# SCH_n2_power_distribution_board_2022-03-.net
KiCad netlist of a schematic drawn in EasyEDA
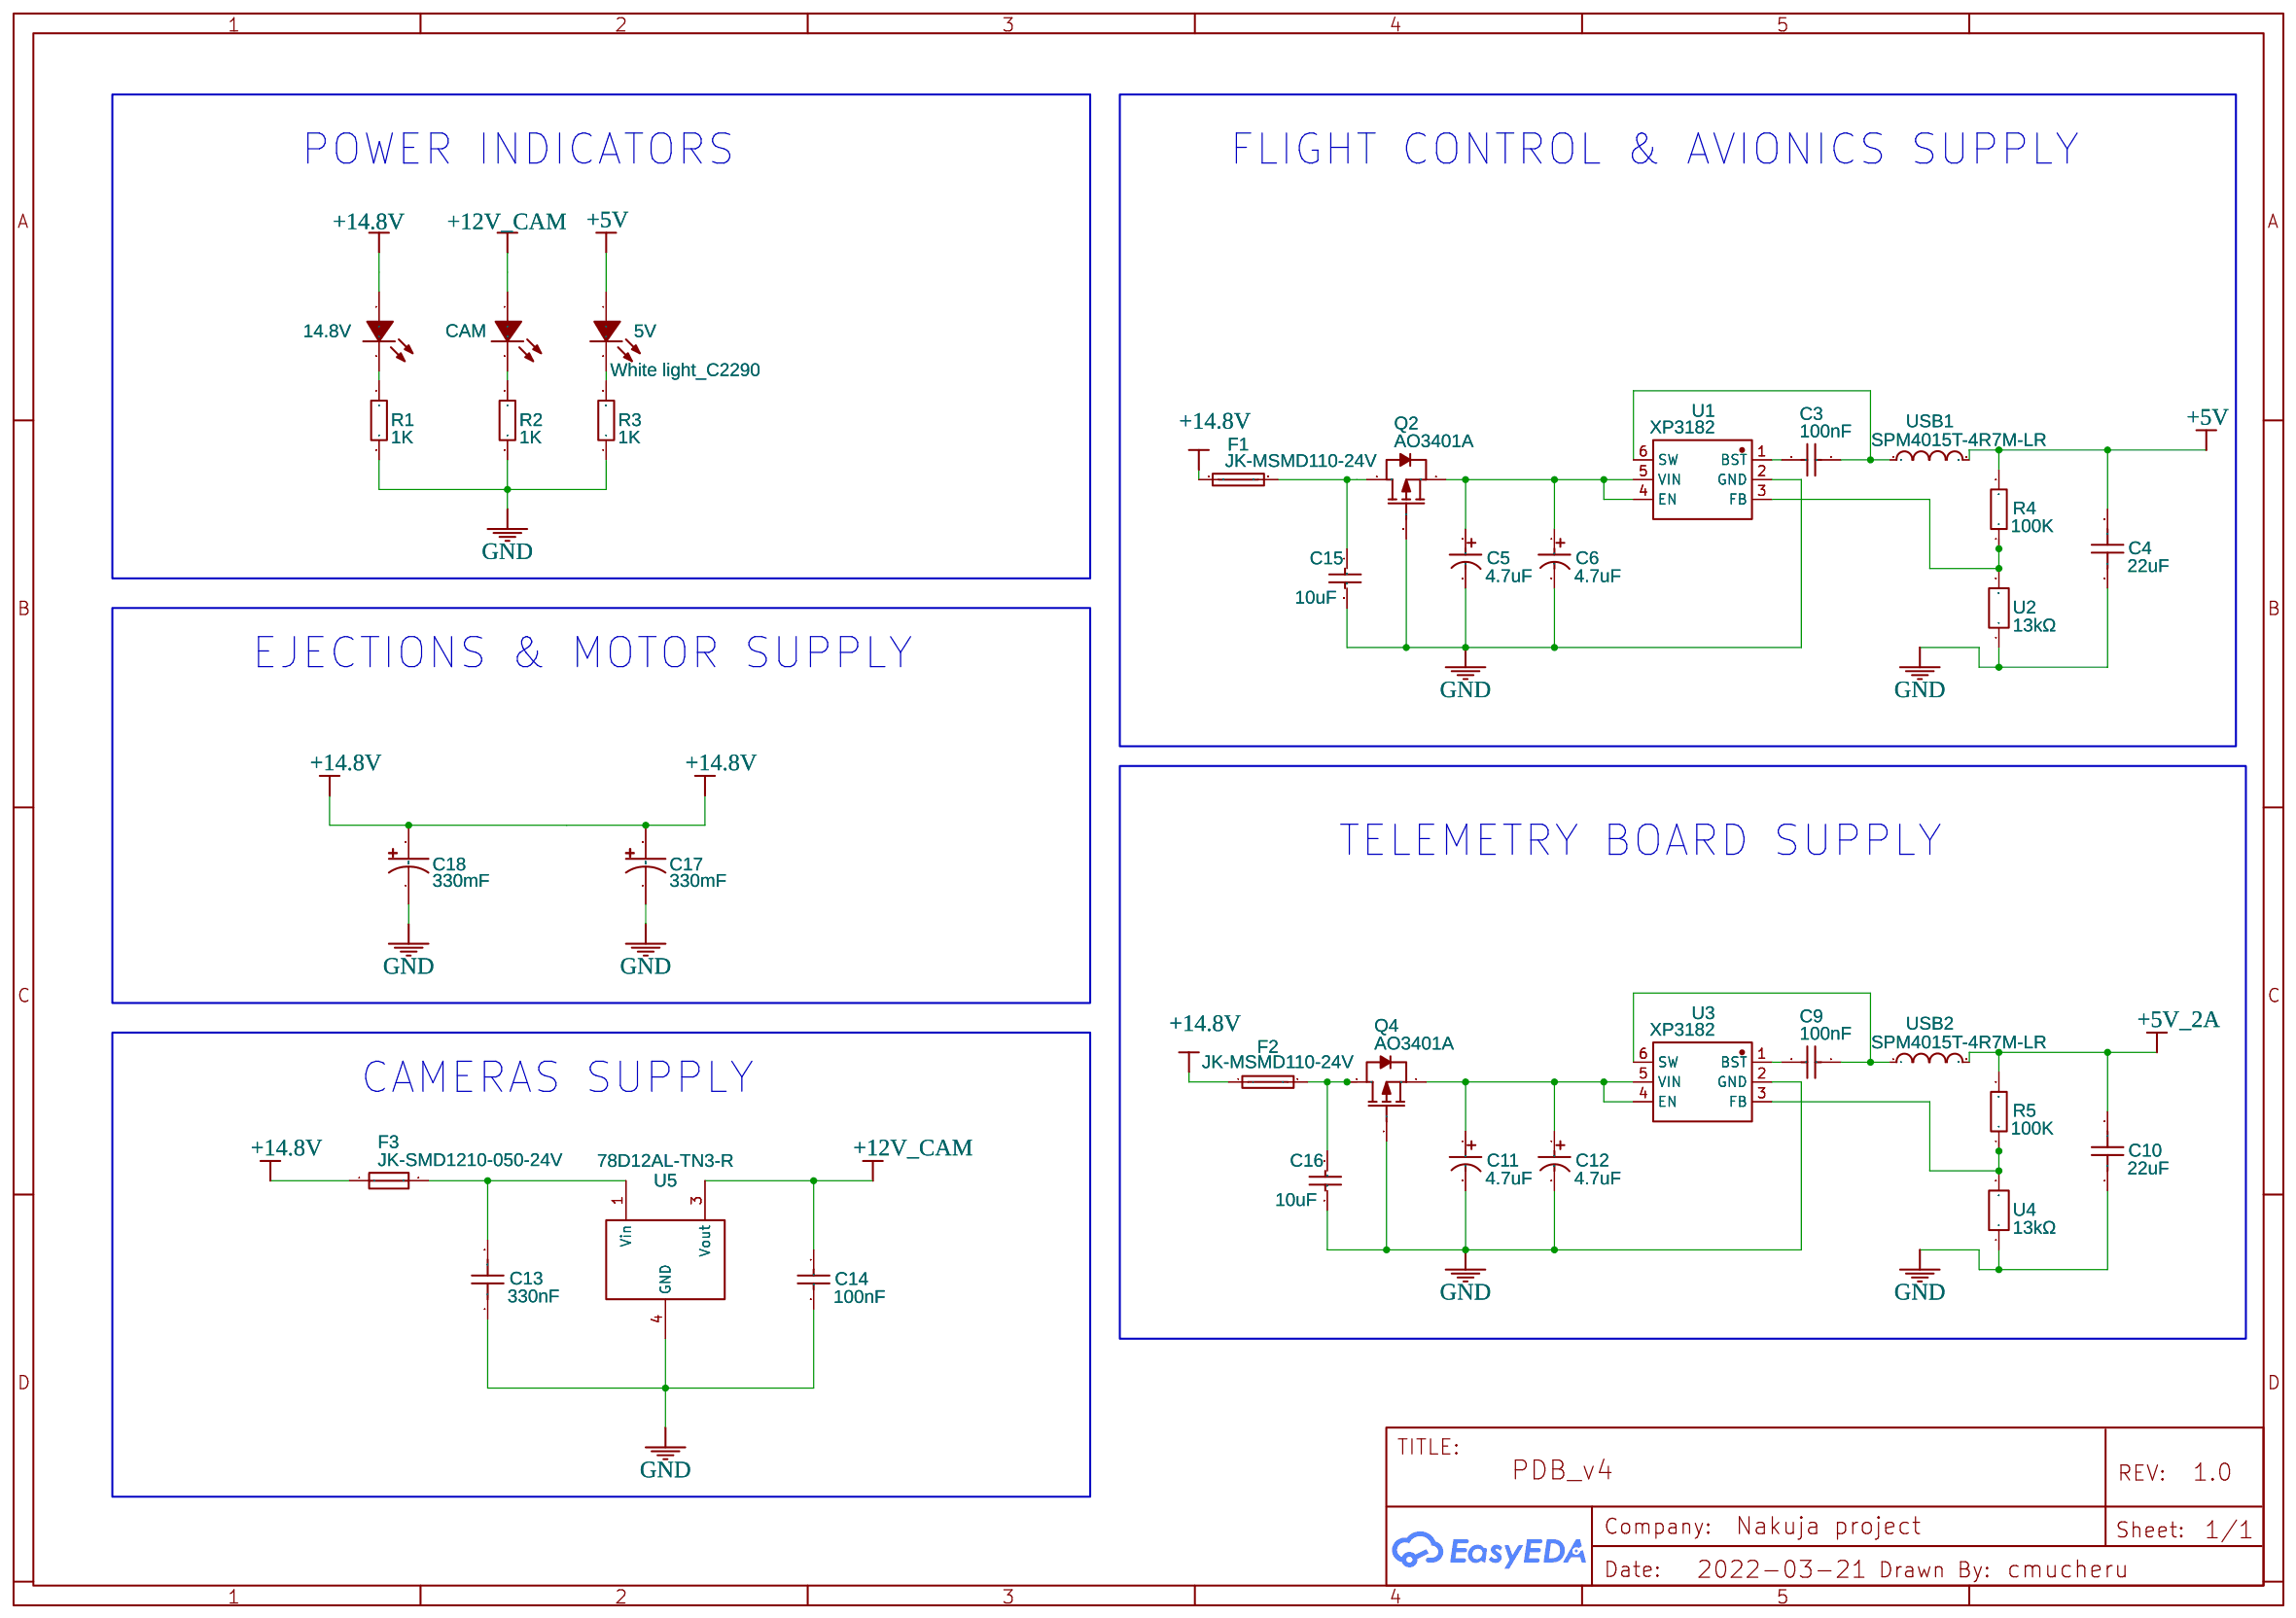
[diagram p0: PDB]
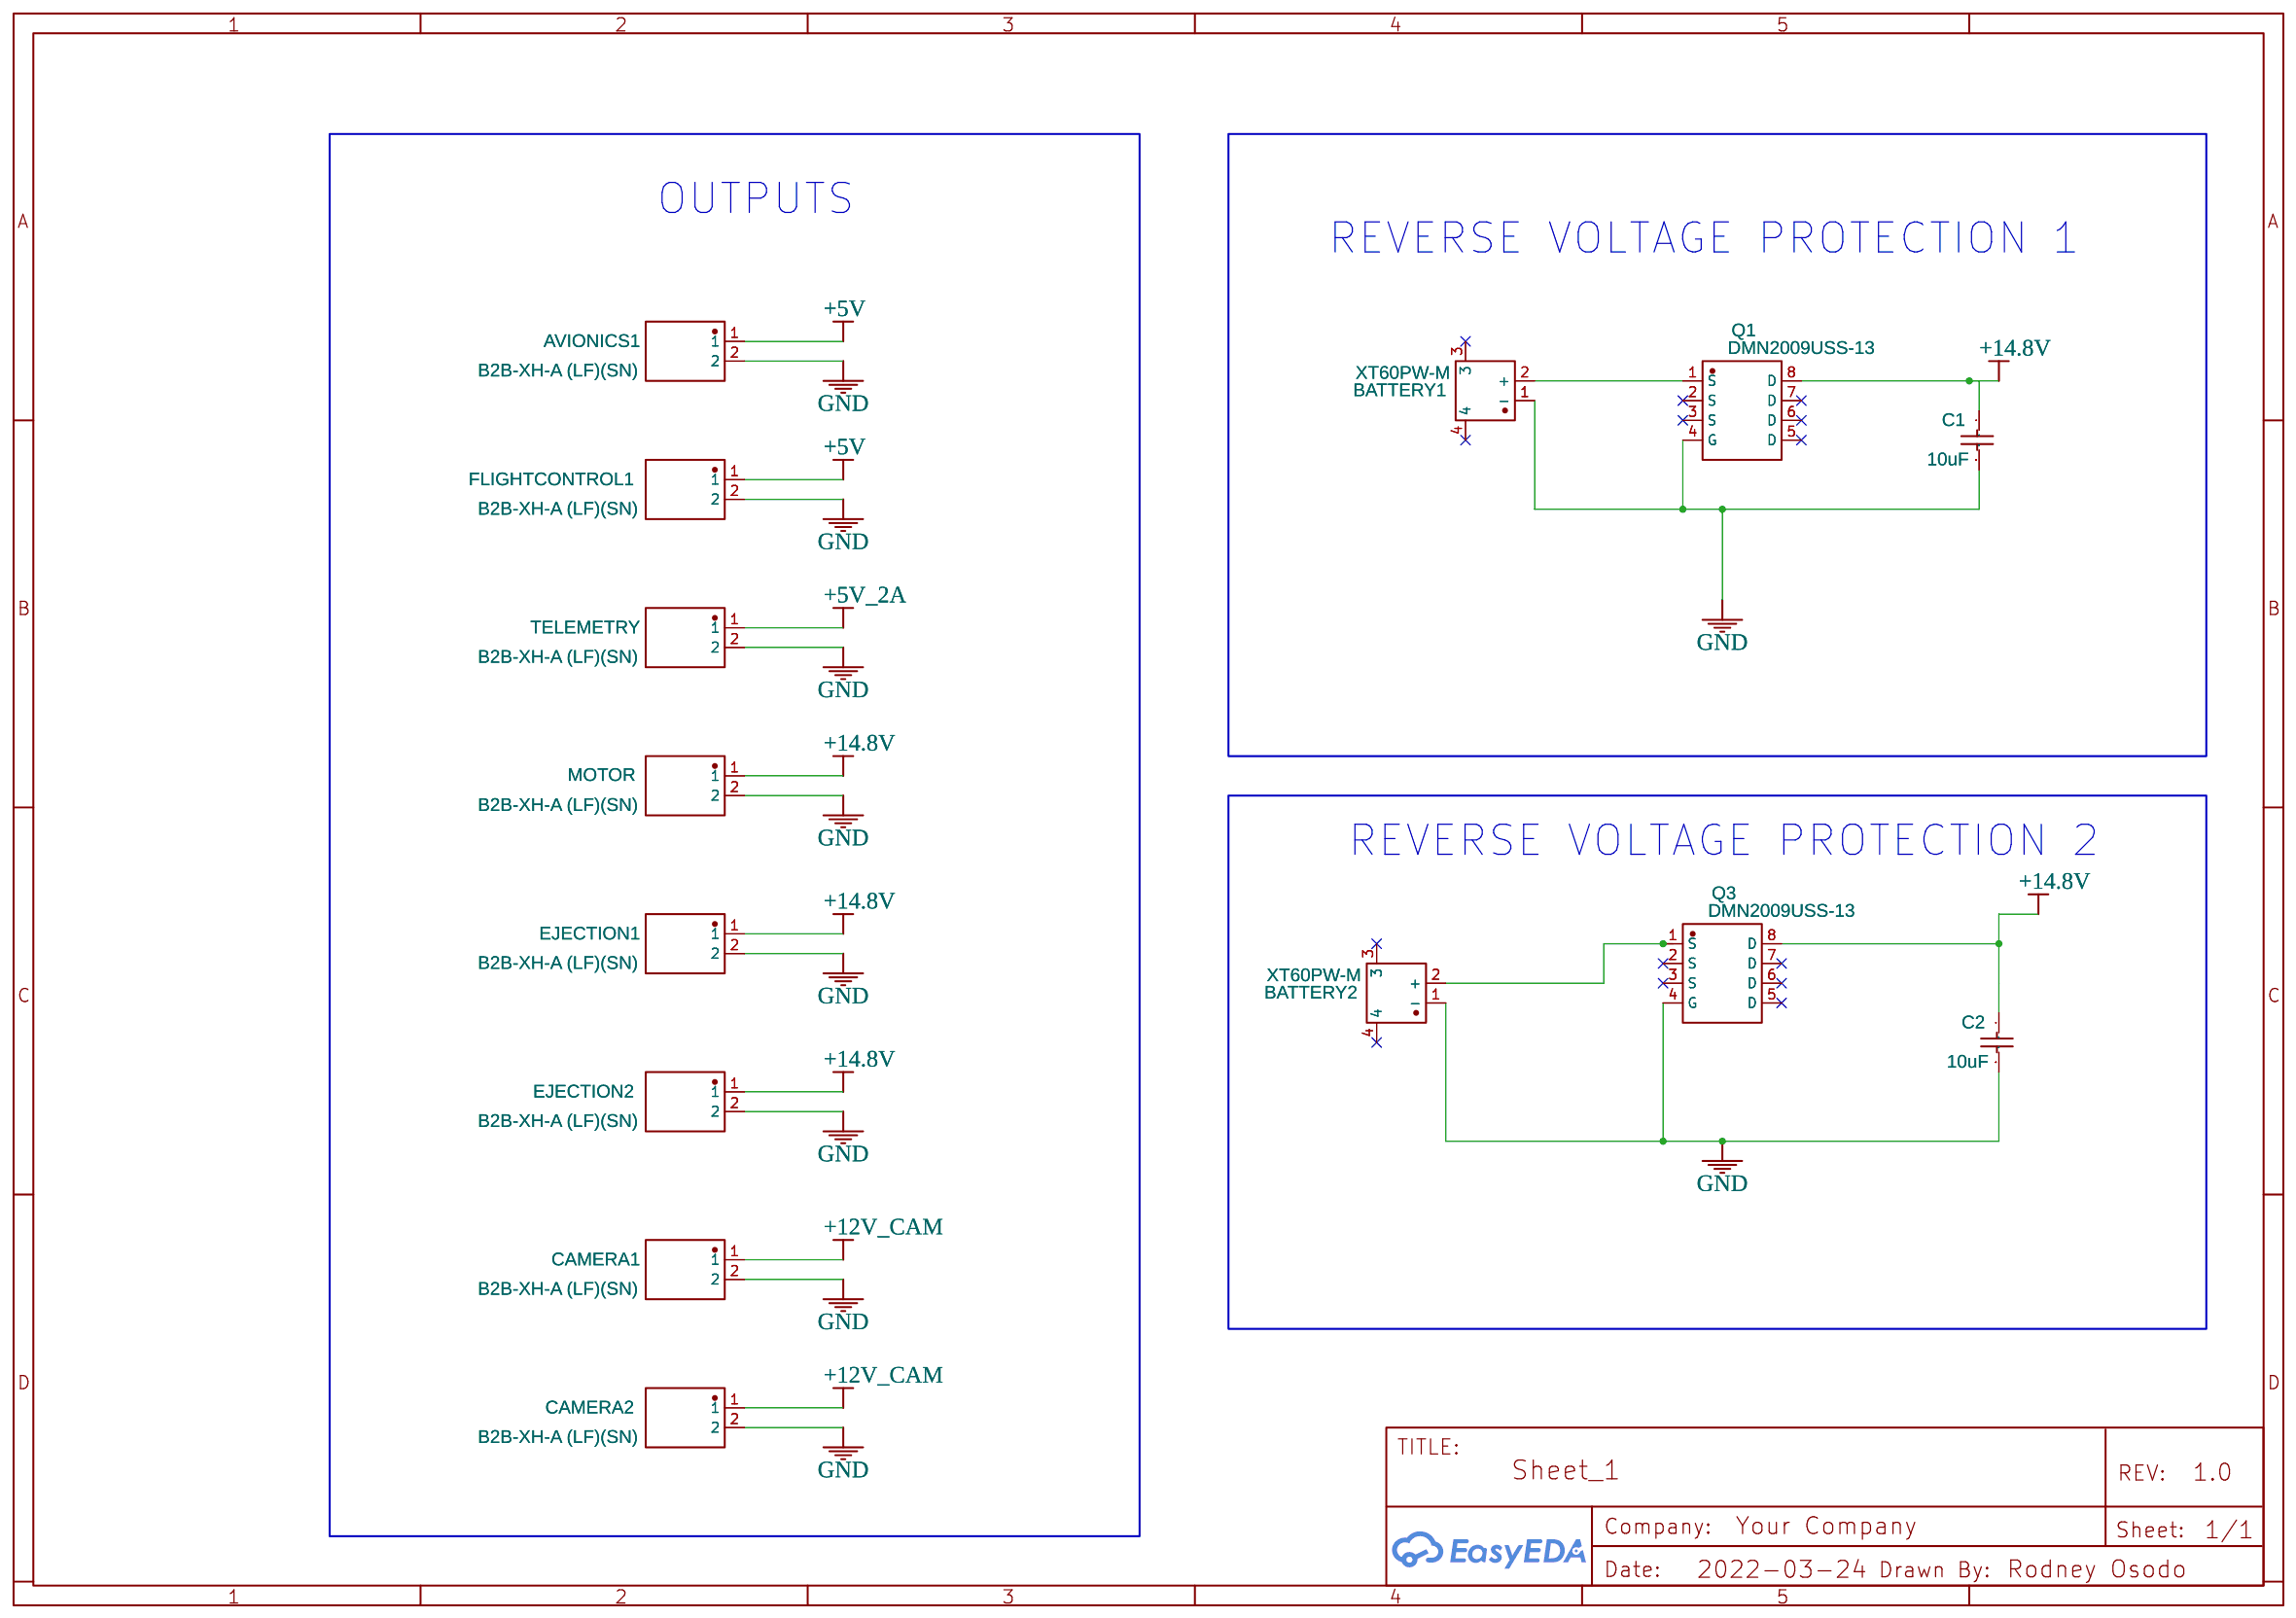
[diagram p1: Connectors]

(export (version "E")
  (design (tool "Eeschema 10.0.6"))
  (components
    (comp (ref "5V")
      (value "White light_C2290")
      (fields
        (field (name "BOM_Manufacturer Part") "0603White light")
        (field (name "BOM_Supplier Part") "C2290")
      )
      (libsource (lib "") (part "0603White light_C2290"))
    )
    (comp (ref "14.8V")
      (value "White light_C2290")
      (fields
        (field (name "BOM_Manufacturer Part") "0603White light")
        (field (name "BOM_Supplier Part") "C2290")
      )
      (libsource (lib "") (part "0603White light_C2290_2"))
    )
    (comp (ref "C3")
      (value "100nF")
      (fields
        (field (name "BOM_Manufacturer Part") "CL05B104KO5NNNC")
        (field (name "BOM_Supplier Part") "C1525")
      )
      (libsource (lib "") (part "CL05B104KO5NNNC_1"))
    )
    (comp (ref "C4")
      (value "22uF")
      (fields
        (field (name "BOM_Manufacturer Part") "GRM155R60J226ME11D")
        (field (name "BOM_Supplier Part") "C415703")
      )
      (libsource (lib "") (part "GRM155R60J226ME11D"))
    )
    (comp (ref "C5")
      (value "4.7uF")
      (fields
        (field (name "BOM_Manufacturer Part") "RVT1V4R7M0405")
        (field (name "BOM_Supplier Part") "C72511")
      )
      (libsource (lib "") (part "RVT1V4R7M0405"))
    )
    (comp (ref "C6")
      (value "4.7uF")
      (fields
        (field (name "BOM_Manufacturer Part") "RVT1V4R7M0405")
        (field (name "BOM_Supplier Part") "C72511")
      )
      (libsource (lib "") (part "RVT1V4R7M0405"))
    )
    (comp (ref "C9")
      (value "100nF")
      (fields
        (field (name "BOM_Manufacturer Part") "CL05B104KO5NNNC")
        (field (name "BOM_Supplier Part") "C1525")
      )
      (libsource (lib "") (part "CL05B104KO5NNNC_1"))
    )
    (comp (ref "C10")
      (value "22uF")
      (fields
        (field (name "BOM_Manufacturer Part") "GRM155R60J226ME11D")
        (field (name "BOM_Supplier Part") "C415703")
      )
      (libsource (lib "") (part "GRM155R60J226ME11D"))
    )
    (comp (ref "C11")
      (value "4.7uF")
      (fields
        (field (name "BOM_Manufacturer Part") "RVT1V4R7M0405")
        (field (name "BOM_Supplier Part") "C72511")
      )
      (libsource (lib "") (part "RVT1V4R7M0405"))
    )
    (comp (ref "C12")
      (value "4.7uF")
      (fields
        (field (name "BOM_Manufacturer Part") "RVT1V4R7M0405")
        (field (name "BOM_Supplier Part") "C72511")
      )
      (libsource (lib "") (part "RVT1V4R7M0405"))
    )
    (comp (ref "C13")
      (value "330nF")
      (fields
        (field (name "BOM_Manufacturer Part") "CC0402ZRY5V7BB334")
        (field (name "BOM_Supplier Part") "C527033")
      )
      (libsource (lib "") (part "CC0402ZRY5V7BB334"))
    )
    (comp (ref "C14")
      (value "100nF")
      (fields
        (field (name "BOM_Manufacturer Part") "CL05B104KO5NNNC")
        (field (name "BOM_Supplier Part") "C1525")
      )
      (libsource (lib "") (part "CL05B104KO5NNNC"))
    )
    (comp (ref "C15")
      (value "10uF")
      (fields
        (field (name "BOM_Manufacturer Part") "CL05A106MQ5NUNC")
        (field (name "BOM_Supplier Part") "C15525")
      )
      (libsource (lib "") (part "CL05A106MQ5NUNC"))
    )
    (comp (ref "C16")
      (value "10uF")
      (fields
        (field (name "BOM_Manufacturer Part") "CL05A106MQ5NUNC")
        (field (name "BOM_Supplier Part") "C15525")
      )
      (libsource (lib "") (part "CL05A106MQ5NUNC"))
    )
    (comp (ref "C17")
      (value "330mF")
      (fields
        (field (name "BOM_Manufacturer Part") "EECS0HD334H")
        (field (name "BOM_Supplier Part") "C128528")
      )
      (libsource (lib "") (part "EECS0HD334H_1"))
    )
    (comp (ref "C18")
      (value "330mF")
      (fields
        (field (name "BOM_Manufacturer Part") "EECS0HD334H")
        (field (name "BOM_Supplier Part") "C128528")
      )
      (libsource (lib "") (part "EECS0HD334H"))
    )
    (comp (ref "CAM")
      (value "White light_C2290")
      (fields
        (field (name "BOM_Manufacturer Part") "0603White light")
        (field (name "BOM_Supplier Part") "C2290")
      )
      (libsource (lib "") (part "0603White light_C2290_1"))
    )
    (comp (ref "F1")
      (value "JK-MSMD110-24V")
      (fields (field (name "BOM_Supplier Part") "C369172"))
      (libsource (lib "") (part "JK-MSMD110-24V"))
    )
    (comp (ref "F2")
      (value "JK-MSMD110-24V")
      (fields (field (name "BOM_Supplier Part") "C369172"))
      (libsource (lib "") (part "JK-MSMD110-24V"))
    )
    (comp (ref "F3")
      (value "JK-SMD1210-050-24V")
      (fields (field (name "BOM_Supplier Part") "C720078"))
      (libsource (lib "") (part "JK-SMD1210-050-24V"))
    )
    (comp (ref "Q2")
      (value "AO3401A")
      (fields (field (name "BOM_Supplier Part") "C15127"))
      (libsource (lib "") (part "AO3401A"))
    )
    (comp (ref "Q4")
      (value "AO3401A")
      (fields (field (name "BOM_Supplier Part") "C15127"))
      (libsource (lib "") (part "AO3401A"))
    )
    (comp (ref "R1")
      (value "1K")
      (fields
        (field (name "BOM_Manufacturer Part") "0402WGF5101TCE")
        (field (name "BOM_Supplier Part") "C25905")
      )
      (libsource (lib "") (part "0402WGF5101TCE"))
    )
    (comp (ref "R2")
      (value "1K")
      (fields
        (field (name "BOM_Manufacturer Part") "0402WGF5101TCE")
        (field (name "BOM_Supplier Part") "C25905")
      )
      (libsource (lib "") (part "0402WGF5101TCE"))
    )
    (comp (ref "R3")
      (value "1K")
      (fields
        (field (name "BOM_Manufacturer Part") "0402WGF5101TCE")
        (field (name "BOM_Supplier Part") "C25905")
      )
      (libsource (lib "") (part "0402WGF5101TCE_1"))
    )
    (comp (ref "R4")
      (value "100K")
      (fields
        (field (name "BOM_Manufacturer Part") "0402WGF1003TCE")
        (field (name "BOM_Supplier Part") "C25741")
      )
      (libsource (lib "") (part "0402WGF1003TCE"))
    )
    (comp (ref "R5")
      (value "100K")
      (fields
        (field (name "BOM_Manufacturer Part") "0402WGF1003TCE")
        (field (name "BOM_Supplier Part") "C25741")
      )
      (libsource (lib "") (part "0402WGF1003TCE"))
    )
    (comp (ref "U1")
      (value "XP3182")
      (fields (field (name "BOM_Supplier Part") "C2802261"))
      (libsource (lib "") (part "XP3182"))
    )
    (comp (ref "U2")
      (value "13kΩ")
      (fields
        (field (name "BOM_Manufacturer Part") "PTFR0402B13K0P9")
        (field (name "BOM_Supplier Part") "C2693072")
      )
      (libsource (lib "") (part "PTFR0402B13K0P9"))
    )
    (comp (ref "U3")
      (value "XP3182")
      (fields (field (name "BOM_Supplier Part") "C2802261"))
      (libsource (lib "") (part "XP3182"))
    )
    (comp (ref "U4")
      (value "13kΩ")
      (fields
        (field (name "BOM_Manufacturer Part") "PTFR0402B13K0P9")
        (field (name "BOM_Supplier Part") "C2693072")
      )
      (libsource (lib "") (part "PTFR0402B13K0P9"))
    )
    (comp (ref "U5")
      (value "78D12AL-TN3-R")
      (fields (field (name "BOM_Supplier Part") "C73290"))
      (libsource (lib "") (part "78D12AL-TN3-R"))
    )
    (comp (ref "USB1")
      (value "SPM4015T-4R7M-LR")
      (fields (field (name "BOM_Supplier Part") "C2052599"))
      (libsource (lib "") (part "SPM4015T-4R7M-LR"))
    )
    (comp (ref "USB2")
      (value "SPM4015T-4R7M-LR")
      (fields (field (name "BOM_Supplier Part") "C2052599"))
      (libsource (lib "") (part "SPM4015T-4R7M-LR"))
    )
    (comp (ref "AVIONICS1")
      (value "B2B-XH-A (LF)(SN)")
      (fields (field (name "BOM_Supplier Part") "C158012"))
      (libsource (lib "") (part "B2B-XH-A (LF)(SN)"))
    )
    (comp (ref "BATTERY1")
      (value "XT60PW-M")
      (fields (field (name "BOM_Supplier Part") "C98732"))
      (libsource (lib "") (part "XT60PW-M"))
    )
    (comp (ref "BATTERY2")
      (value "XT60PW-M")
      (fields (field (name "BOM_Supplier Part") "C98732"))
      (libsource (lib "") (part "XT60PW-M"))
    )
    (comp (ref "C1")
      (value "10uF")
      (fields
        (field (name "BOM_Manufacturer Part") "CL05A106MQ5NUNC")
        (field (name "BOM_Supplier Part") "C15525")
      )
      (libsource (lib "") (part "CL05A106MQ5NUNC"))
    )
    (comp (ref "C2")
      (value "10uF")
      (fields
        (field (name "BOM_Manufacturer Part") "CL05A106MQ5NUNC")
        (field (name "BOM_Supplier Part") "C15525")
      )
      (libsource (lib "") (part "CL05A106MQ5NUNC"))
    )
    (comp (ref "CAMERA1")
      (value "B2B-XH-A (LF)(SN)")
      (fields (field (name "BOM_Supplier Part") "C158012"))
      (libsource (lib "") (part "B2B-XH-A (LF)(SN)_2"))
    )
    (comp (ref "CAMERA2")
      (value "B2B-XH-A (LF)(SN)")
      (fields (field (name "BOM_Supplier Part") "C158012"))
      (libsource (lib "") (part "B2B-XH-A (LF)(SN)_2"))
    )
    (comp (ref "EJECTION1")
      (value "B2B-XH-A (LF)(SN)")
      (fields (field (name "BOM_Supplier Part") "C158012"))
      (libsource (lib "") (part "B2B-XH-A (LF)(SN)_1"))
    )
    (comp (ref "EJECTION2")
      (value "B2B-XH-A (LF)(SN)")
      (fields (field (name "BOM_Supplier Part") "C158012"))
      (libsource (lib "") (part "B2B-XH-A (LF)(SN)_1"))
    )
    (comp (ref "FLIGHTCONTROL1")
      (value "B2B-XH-A (LF)(SN)")
      (fields (field (name "BOM_Supplier Part") "C158012"))
      (libsource (lib "") (part "B2B-XH-A (LF)(SN)_4"))
    )
    (comp (ref "MOTOR")
      (value "B2B-XH-A (LF)(SN)")
      (fields (field (name "BOM_Supplier Part") "C158012"))
      (libsource (lib "") (part "B2B-XH-A (LF)(SN)_5"))
    )
    (comp (ref "Q1")
      (value "DMN2009USS-13")
      (fields (field (name "BOM_Supplier Part") "C460995"))
      (libsource (lib "") (part "DMN2009USS-13"))
    )
    (comp (ref "Q3")
      (value "DMN2009USS-13")
      (fields (field (name "BOM_Supplier Part") "C460995"))
      (libsource (lib "") (part "DMN2009USS-13"))
    )
    (comp (ref "TELEMETRY")
      (value "B2B-XH-A (LF)(SN)")
      (fields (field (name "BOM_Supplier Part") "C158012"))
      (libsource (lib "") (part "B2B-XH-A (LF)(SN)_3"))
    )
  )
  (nets
    (net (code "1") (name "+5V") (class "Default")
      (node (ref "5V") (pin "1") (pinfunction "A_1") (pintype "unspecified"))
      (node (ref "AVIONICS1") (pin "1") (pinfunction "1_1") (pintype "unspecified"))
      (node (ref "C4") (pin "2") (pinfunction "2_2") (pintype "unspecified"))
      (node (ref "FLIGHTCONTROL1") (pin "1") (pinfunction "1_1") (pintype "unspecified"))
      (node (ref "R4") (pin "2") (pinfunction "2_2") (pintype "input"))
      (node (ref "USB1") (pin "2") (pinfunction "2_2") (pintype "unspecified"))
    )
    (net (code "2") (name "+5V_2A") (class "Default")
      (node (ref "C10") (pin "2") (pinfunction "2_2") (pintype "unspecified"))
      (node (ref "R5") (pin "2") (pinfunction "2_2") (pintype "input"))
      (node (ref "TELEMETRY") (pin "1") (pinfunction "1_1") (pintype "unspecified"))
      (node (ref "USB2") (pin "2") (pinfunction "2_2") (pintype "unspecified"))
    )
    (net (code "3") (name "+12V_CAM") (class "Default")
      (node (ref "C14") (pin "1") (pinfunction "1_1") (pintype "input"))
      (node (ref "CAM") (pin "1") (pinfunction "A_1") (pintype "unspecified"))
      (node (ref "CAMERA1") (pin "1") (pinfunction "1_1") (pintype "unspecified"))
      (node (ref "CAMERA2") (pin "1") (pinfunction "1_1") (pintype "unspecified"))
      (node (ref "U5") (pin "3") (pinfunction "Vout_3") (pintype "unspecified"))
    )
    (net (code "4") (name "+14.8V") (class "Default")
      (node (ref "14.8V") (pin "1") (pinfunction "A_1") (pintype "unspecified"))
      (node (ref "C1") (pin "1") (pinfunction "1_1") (pintype "input"))
      (node (ref "C17") (pin "1") (pinfunction "1_1") (pintype "unspecified"))
      (node (ref "C18") (pin "1") (pinfunction "1_1") (pintype "unspecified"))
      (node (ref "C2") (pin "1") (pinfunction "1_1") (pintype "input"))
      (node (ref "EJECTION1") (pin "1") (pinfunction "1_1") (pintype "unspecified"))
      (node (ref "EJECTION2") (pin "1") (pinfunction "1_1") (pintype "unspecified"))
      (node (ref "F1") (pin "1") (pinfunction "1_1") (pintype "unspecified"))
      (node (ref "F2") (pin "1") (pinfunction "1_1") (pintype "unspecified"))
      (node (ref "F3") (pin "1") (pinfunction "1_1") (pintype "unspecified"))
      (node (ref "MOTOR") (pin "1") (pinfunction "1_1") (pintype "unspecified"))
      (node (ref "Q1") (pin "8") (pinfunction "D_8") (pintype "unspecified"))
      (node (ref "Q3") (pin "8") (pinfunction "D_8") (pintype "unspecified"))
    )
    (net (code "5") (name "GND") (class "Default")
      (node (ref "AVIONICS1") (pin "2") (pinfunction "2_2") (pintype "unspecified"))
      (node (ref "BATTERY1") (pin "1") (pinfunction "-_1") (pintype "unspecified"))
      (node (ref "BATTERY2") (pin "1") (pinfunction "-_1") (pintype "unspecified"))
      (node (ref "C1") (pin "2") (pinfunction "2_2") (pintype "input"))
      (node (ref "C10") (pin "1") (pinfunction "1_1") (pintype "unspecified"))
      (node (ref "C11") (pin "2") (pinfunction "2_2") (pintype "input"))
      (node (ref "C12") (pin "2") (pinfunction "2_2") (pintype "input"))
      (node (ref "C13") (pin "1") (pinfunction "1_1") (pintype "unspecified"))
      (node (ref "C14") (pin "2") (pinfunction "2_2") (pintype "input"))
      (node (ref "C15") (pin "2") (pinfunction "2_2") (pintype "input"))
      (node (ref "C16") (pin "2") (pinfunction "2_2") (pintype "input"))
      (node (ref "C17") (pin "2") (pinfunction "2_2") (pintype "unspecified"))
      (node (ref "C18") (pin "2") (pinfunction "2_2") (pintype "unspecified"))
      (node (ref "C2") (pin "2") (pinfunction "2_2") (pintype "input"))
      (node (ref "C4") (pin "1") (pinfunction "1_1") (pintype "unspecified"))
      (node (ref "C5") (pin "2") (pinfunction "2_2") (pintype "input"))
      (node (ref "C6") (pin "2") (pinfunction "2_2") (pintype "input"))
      (node (ref "CAMERA1") (pin "2") (pinfunction "2_2") (pintype "unspecified"))
      (node (ref "CAMERA2") (pin "2") (pinfunction "2_2") (pintype "unspecified"))
      (node (ref "EJECTION1") (pin "2") (pinfunction "2_2") (pintype "unspecified"))
      (node (ref "EJECTION2") (pin "2") (pinfunction "2_2") (pintype "unspecified"))
      (node (ref "FLIGHTCONTROL1") (pin "2") (pinfunction "2_2") (pintype "unspecified"))
      (node (ref "MOTOR") (pin "2") (pinfunction "2_2") (pintype "unspecified"))
      (node (ref "Q1") (pin "4") (pinfunction "G_4") (pintype "unspecified"))
      (node (ref "Q2") (pin "1") (pinfunction "G_1") (pintype "unspecified"))
      (node (ref "Q3") (pin "4") (pinfunction "G_4") (pintype "unspecified"))
      (node (ref "Q4") (pin "1") (pinfunction "G_1") (pintype "unspecified"))
      (node (ref "R1") (pin "2") (pinfunction "2_2") (pintype "input"))
      (node (ref "R2") (pin "2") (pinfunction "2_2") (pintype "input"))
      (node (ref "R3") (pin "1") (pinfunction "1_1") (pintype "input"))
      (node (ref "TELEMETRY") (pin "2") (pinfunction "2_2") (pintype "unspecified"))
      (node (ref "U1") (pin "2") (pinfunction "GND_2") (pintype "unspecified"))
      (node (ref "U2") (pin "1") (pinfunction "1_1") (pintype "unspecified"))
      (node (ref "U3") (pin "2") (pinfunction "GND_2") (pintype "unspecified"))
      (node (ref "U4") (pin "1") (pinfunction "1_1") (pintype "unspecified"))
      (node (ref "U5") (pin "4") (pinfunction "GND_4") (pintype "unspecified"))
    )
    (net (code "6") (name "Net-(5V-K)") (class "Default")
      (node (ref "5V") (pin "2") (pinfunction "K_2") (pintype "unspecified"))
      (node (ref "R3") (pin "2") (pinfunction "2_2") (pintype "input"))
    )
    (net (code "7") (name "Net-(14.8V-K)") (class "Default")
      (node (ref "14.8V") (pin "2") (pinfunction "K_2") (pintype "unspecified"))
      (node (ref "R1") (pin "1") (pinfunction "1_1") (pintype "input"))
    )
    (net (code "8") (name "Net-(BATTERY1-+)") (class "Default")
      (node (ref "BATTERY1") (pin "2") (pinfunction "+_2") (pintype "unspecified"))
      (node (ref "Q1") (pin "1") (pinfunction "S_1") (pintype "unspecified"))
    )
    (net (code "9") (name "Net-(BATTERY2-+)") (class "Default")
      (node (ref "BATTERY2") (pin "2") (pinfunction "+_2") (pintype "unspecified"))
      (node (ref "Q3") (pin "1") (pinfunction "S_1") (pintype "unspecified"))
    )
    (net (code "10") (name "Net-(CAM-K)") (class "Default")
      (node (ref "CAM") (pin "2") (pinfunction "K_2") (pintype "unspecified"))
      (node (ref "R2") (pin "1") (pinfunction "1_1") (pintype "input"))
    )
    (net (code "11") (name "Net-(Q2-D)") (class "Default")
      (node (ref "C15") (pin "1") (pinfunction "1_1") (pintype "input"))
      (node (ref "F1") (pin "2") (pinfunction "2_2") (pintype "unspecified"))
      (node (ref "Q2") (pin "3") (pinfunction "D_3") (pintype "unspecified"))
    )
    (net (code "12") (name "Net-(Q2-S)") (class "Default")
      (node (ref "C5") (pin "1") (pinfunction "1_1") (pintype "input"))
      (node (ref "C6") (pin "1") (pinfunction "1_1") (pintype "input"))
      (node (ref "Q2") (pin "2") (pinfunction "S_2") (pintype "unspecified"))
      (node (ref "U1") (pin "4") (pinfunction "EN_4") (pintype "unspecified"))
      (node (ref "U1") (pin "5") (pinfunction "VIN_5") (pintype "unspecified"))
    )
    (net (code "13") (name "Net-(Q4-D)") (class "Default")
      (node (ref "C16") (pin "1") (pinfunction "1_1") (pintype "input"))
      (node (ref "F2") (pin "2") (pinfunction "2_2") (pintype "unspecified"))
      (node (ref "Q4") (pin "3") (pinfunction "D_3") (pintype "unspecified"))
    )
    (net (code "14") (name "Net-(Q4-S)") (class "Default")
      (node (ref "C11") (pin "1") (pinfunction "1_1") (pintype "input"))
      (node (ref "C12") (pin "1") (pinfunction "1_1") (pintype "input"))
      (node (ref "Q4") (pin "2") (pinfunction "S_2") (pintype "unspecified"))
      (node (ref "U3") (pin "4") (pinfunction "EN_4") (pintype "unspecified"))
      (node (ref "U3") (pin "5") (pinfunction "VIN_5") (pintype "unspecified"))
    )
    (net (code "15") (name "Net-(U1-BST)") (class "Default")
      (node (ref "C3") (pin "2") (pinfunction "2_2") (pintype "input"))
      (node (ref "U1") (pin "1") (pinfunction "BST_1") (pintype "unspecified"))
    )
    (net (code "16") (name "Net-(U1-FB)") (class "Default")
      (node (ref "R4") (pin "1") (pinfunction "1_1") (pintype "input"))
      (node (ref "U1") (pin "3") (pinfunction "FB_3") (pintype "unspecified"))
      (node (ref "U2") (pin "2") (pinfunction "2_2") (pintype "unspecified"))
    )
    (net (code "17") (name "Net-(U1-SW)") (class "Default")
      (node (ref "C3") (pin "1") (pinfunction "1_1") (pintype "input"))
      (node (ref "U1") (pin "6") (pinfunction "SW_6") (pintype "unspecified"))
      (node (ref "USB1") (pin "1") (pinfunction "1_1") (pintype "unspecified"))
    )
    (net (code "18") (name "Net-(U3-BST)") (class "Default")
      (node (ref "C9") (pin "2") (pinfunction "2_2") (pintype "input"))
      (node (ref "U3") (pin "1") (pinfunction "BST_1") (pintype "unspecified"))
    )
    (net (code "19") (name "Net-(U3-FB)") (class "Default")
      (node (ref "R5") (pin "1") (pinfunction "1_1") (pintype "input"))
      (node (ref "U3") (pin "3") (pinfunction "FB_3") (pintype "unspecified"))
      (node (ref "U4") (pin "2") (pinfunction "2_2") (pintype "unspecified"))
    )
    (net (code "20") (name "Net-(U3-SW)") (class "Default")
      (node (ref "C9") (pin "1") (pinfunction "1_1") (pintype "input"))
      (node (ref "U3") (pin "6") (pinfunction "SW_6") (pintype "unspecified"))
      (node (ref "USB2") (pin "1") (pinfunction "1_1") (pintype "unspecified"))
    )
    (net (code "21") (name "Net-(U5-Vin)") (class "Default")
      (node (ref "C13") (pin "2") (pinfunction "2_2") (pintype "unspecified"))
      (node (ref "F3") (pin "2") (pinfunction "2_2") (pintype "unspecified"))
      (node (ref "U5") (pin "1") (pinfunction "Vin_1") (pintype "unspecified"))
    )
    (net (code "22") (name "unconnected-(BATTERY1-Pad3)") (class "Default")
      (node (ref "BATTERY1") (pin "3") (pinfunction "3_3") (pintype "unspecified+no_connect"))
    )
    (net (code "23") (name "unconnected-(BATTERY1-Pad4)") (class "Default")
      (node (ref "BATTERY1") (pin "4") (pinfunction "4_4") (pintype "unspecified+no_connect"))
    )
    (net (code "24") (name "unconnected-(BATTERY2-Pad3)") (class "Default")
      (node (ref "BATTERY2") (pin "3") (pinfunction "3_3") (pintype "unspecified+no_connect"))
    )
    (net (code "25") (name "unconnected-(BATTERY2-Pad4)") (class "Default")
      (node (ref "BATTERY2") (pin "4") (pinfunction "4_4") (pintype "unspecified+no_connect"))
    )
    (net (code "26") (name "unconnected-(Q1-D-Pad5)") (class "Default")
      (node (ref "Q1") (pin "5") (pinfunction "D_5") (pintype "unspecified+no_connect"))
    )
    (net (code "27") (name "unconnected-(Q1-D-Pad6)") (class "Default")
      (node (ref "Q1") (pin "6") (pinfunction "D_6") (pintype "unspecified+no_connect"))
    )
    (net (code "28") (name "unconnected-(Q1-D-Pad7)") (class "Default")
      (node (ref "Q1") (pin "7") (pinfunction "D_7") (pintype "unspecified+no_connect"))
    )
    (net (code "29") (name "unconnected-(Q1-S-Pad2)") (class "Default")
      (node (ref "Q1") (pin "2") (pinfunction "S_2") (pintype "unspecified+no_connect"))
    )
    (net (code "30") (name "unconnected-(Q1-S-Pad3)") (class "Default")
      (node (ref "Q1") (pin "3") (pinfunction "S_3") (pintype "unspecified+no_connect"))
    )
    (net (code "31") (name "unconnected-(Q3-D-Pad5)") (class "Default")
      (node (ref "Q3") (pin "5") (pinfunction "D_5") (pintype "unspecified+no_connect"))
    )
    (net (code "32") (name "unconnected-(Q3-D-Pad6)") (class "Default")
      (node (ref "Q3") (pin "6") (pinfunction "D_6") (pintype "unspecified+no_connect"))
    )
    (net (code "33") (name "unconnected-(Q3-D-Pad7)") (class "Default")
      (node (ref "Q3") (pin "7") (pinfunction "D_7") (pintype "unspecified+no_connect"))
    )
    (net (code "34") (name "unconnected-(Q3-S-Pad2)") (class "Default")
      (node (ref "Q3") (pin "2") (pinfunction "S_2") (pintype "unspecified+no_connect"))
    )
    (net (code "35") (name "unconnected-(Q3-S-Pad3)") (class "Default")
      (node (ref "Q3") (pin "3") (pinfunction "S_3") (pintype "unspecified+no_connect"))
    )
  )
)
